# Power_Distribution_-_Solar_Sense_Telemet.net
KiCad netlist of a schematic drawn in Altium Designer
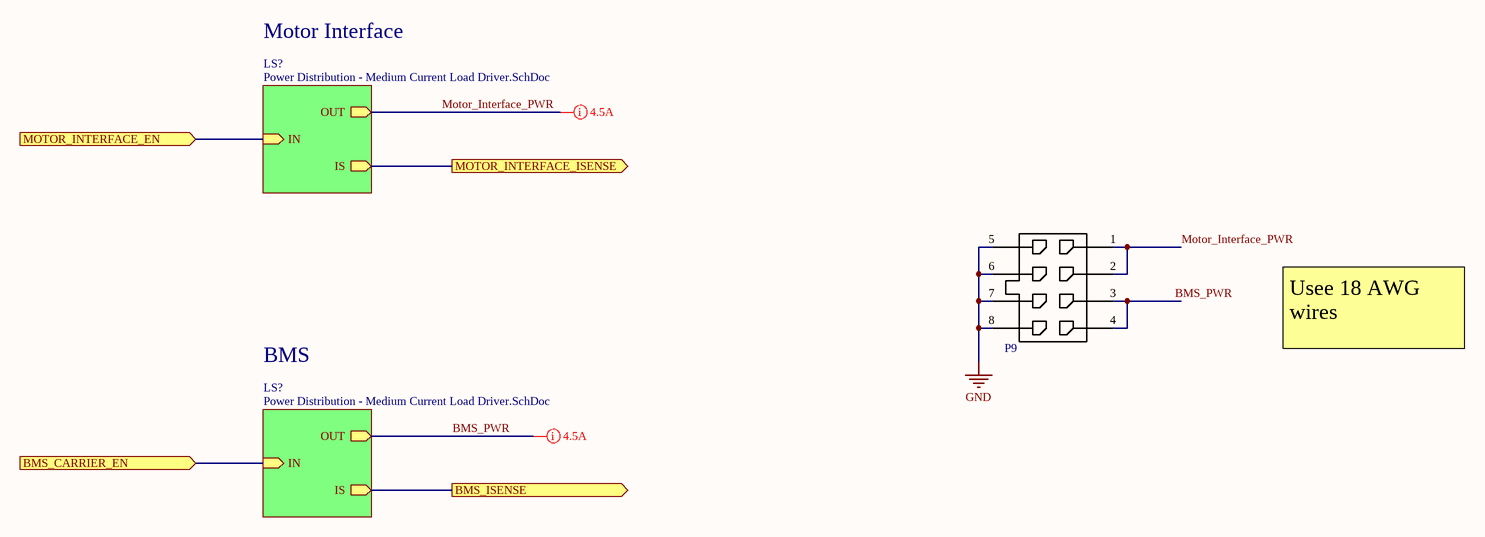
[diagram p0: Power Distribution - Solar Sense, Telemetry, and Motor Interface.SchDoc]

(export (version "E")
  (design (tool "Eeschema 10.0.6"))
  (components
    (comp (ref "P9")
      (value "CONN 8POS MICRO-FIT 3mm")
      (footprint "CONN, 8POS MICRO-FIT")
      (description "Connector Header Through Hole 6 position 0.118\" (3.00mm)")
      (fields
        (field (name "MANUFACTURER") "Molex, LLC")
        (field (name "MANUFACTURER PART NUMBER") "0430450827")
      )
      (libsource (lib "Schematic Diagrams") (part "CONN 8POS MICRO-FIT 3mm"))
    )
  )
  (nets
    (net (code "3") (name "/BMS_PWR") (class "Default")
      (node (ref "P9") (pin "3") (pinfunction "3_3") (pintype "passive"))
      (node (ref "P9") (pin "4") (pinfunction "4_4") (pintype "passive"))
    )
    (net (code "6") (name "/Motor_Interface_PWR") (class "Default")
      (node (ref "P9") (pin "1") (pinfunction "1_1") (pintype "passive"))
      (node (ref "P9") (pin "2") (pinfunction "2_2") (pintype "passive"))
    )
    (net (code "7") (name "GND") (class "Default")
      (node (ref "P9") (pin "5") (pinfunction "5_5") (pintype "passive"))
      (node (ref "P9") (pin "6") (pinfunction "6_6") (pintype "passive"))
      (node (ref "P9") (pin "7") (pinfunction "7_7") (pintype "passive"))
      (node (ref "P9") (pin "8") (pinfunction "8_8") (pintype "passive"))
    )
  )
)
